# optical-connection.net
KiCad netlist of a schematic drawn in Altium Designer
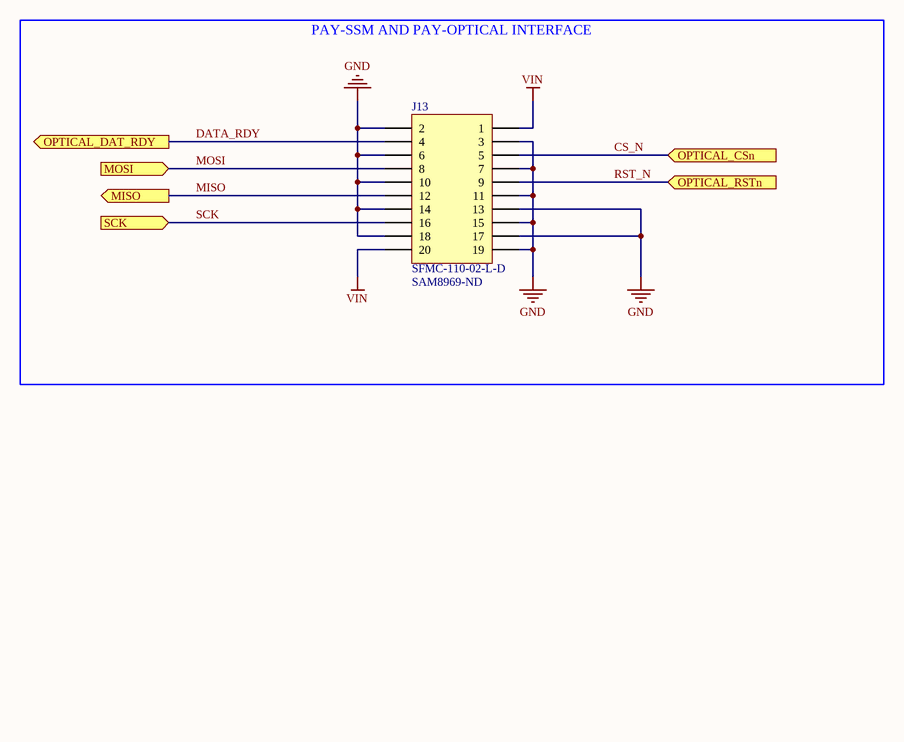
[diagram p0: optical-connection.SchDoc]

(export (version "E")
  (design (tool "Eeschema 10.0.6"))
  (components
    (comp (ref "J13")
      (value "SFMC-110-02-L-D")
      (footprint "SFMC-110-02-L-D")
      (fields (field (name "SUPPLIER PART NUMBER 1") "SAM8969-ND"))
      (libsource (lib "heron-general") (part "SFMC-110-02-L-D"))
    )
  )
  (nets
    (net (code "1") (name "/CS_N") (class "Default")
      (node (ref "J13") (pin "5") (pinfunction "5_5") (pintype "passive"))
    )
    (net (code "2") (name "/DATA_RDY") (class "Default")
      (node (ref "J13") (pin "4") (pinfunction "4_4") (pintype "passive"))
    )
    (net (code "3") (name "/MISO") (class "Default")
      (node (ref "J13") (pin "12") (pinfunction "12_12") (pintype "passive"))
    )
    (net (code "4") (name "/MOSI") (class "Default")
      (node (ref "J13") (pin "8") (pinfunction "8_8") (pintype "passive"))
    )
    (net (code "5") (name "/RST_N") (class "Default")
      (node (ref "J13") (pin "9") (pinfunction "9_9") (pintype "passive"))
    )
    (net (code "6") (name "/SCK") (class "Default")
      (node (ref "J13") (pin "16") (pinfunction "16_16") (pintype "passive"))
    )
    (net (code "7") (name "GND") (class "Default")
      (node (ref "J13") (pin "10") (pinfunction "10_10") (pintype "passive"))
      (node (ref "J13") (pin "11") (pinfunction "11_11") (pintype "passive"))
      (node (ref "J13") (pin "13") (pinfunction "13_13") (pintype "passive"))
      (node (ref "J13") (pin "14") (pinfunction "14_14") (pintype "passive"))
      (node (ref "J13") (pin "15") (pinfunction "15_15") (pintype "passive"))
      (node (ref "J13") (pin "17") (pinfunction "17_17") (pintype "passive"))
      (node (ref "J13") (pin "18") (pinfunction "18_18") (pintype "passive"))
      (node (ref "J13") (pin "19") (pinfunction "19_19") (pintype "passive"))
      (node (ref "J13") (pin "2") (pinfunction "2_2") (pintype "passive"))
      (node (ref "J13") (pin "3") (pinfunction "3_3") (pintype "passive"))
      (node (ref "J13") (pin "6") (pinfunction "6_6") (pintype "passive"))
      (node (ref "J13") (pin "7") (pinfunction "7_7") (pintype "passive"))
    )
    (net (code "8") (name "VIN") (class "Default")
      (node (ref "J13") (pin "1") (pinfunction "1_1") (pintype "passive"))
      (node (ref "J13") (pin "20") (pinfunction "20_20") (pintype "passive"))
    )
  )
)
